# schematic.net
KiCad netlist of a schematic drawn in EAGLE
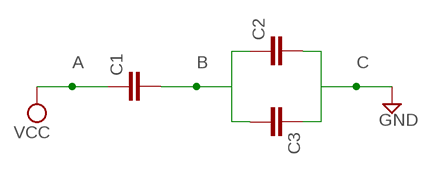
[diagram p0: schematic, sheet 1]

(export (version "E")
  (design (tool "Eeschema 10.0.6"))
  (components
    (comp (ref "C1")
      (value "C5/2.5")
      (footprint "eagle-import:C5B2.5")
      (libsource (lib "eagle-import") (part "C5/2.5"))
    )
    (comp (ref "C2")
      (value "C5/2.5")
      (footprint "eagle-import:C5B2.5")
      (libsource (lib "eagle-import") (part "C5/2.5"))
    )
    (comp (ref "C3")
      (value "C5/2.5")
      (footprint "eagle-import:C5B2.5")
      (libsource (lib "eagle-import") (part "C5/2.5"))
    )
  )
  (nets
    (net (code "1") (name "/B") (class "Default")
      (node (ref "C1") (pin "2") (pinfunction "2_2") (pintype "passive"))
      (node (ref "C2") (pin "1") (pinfunction "1_1") (pintype "passive"))
      (node (ref "C3") (pin "2") (pinfunction "2_2") (pintype "passive"))
    )
    (net (code "2") (name "GND") (class "Default")
      (node (ref "C2") (pin "2") (pinfunction "2_2") (pintype "passive"))
      (node (ref "C3") (pin "1") (pinfunction "1_1") (pintype "passive"))
    )
    (net (code "3") (name "VCC") (class "Default")
      (node (ref "C1") (pin "1") (pinfunction "1_1") (pintype "passive"))
    )
  )
)
